# OnOnfre_Easy_Light_rev1.net
KiCad netlist of a schematic drawn in EAGLE
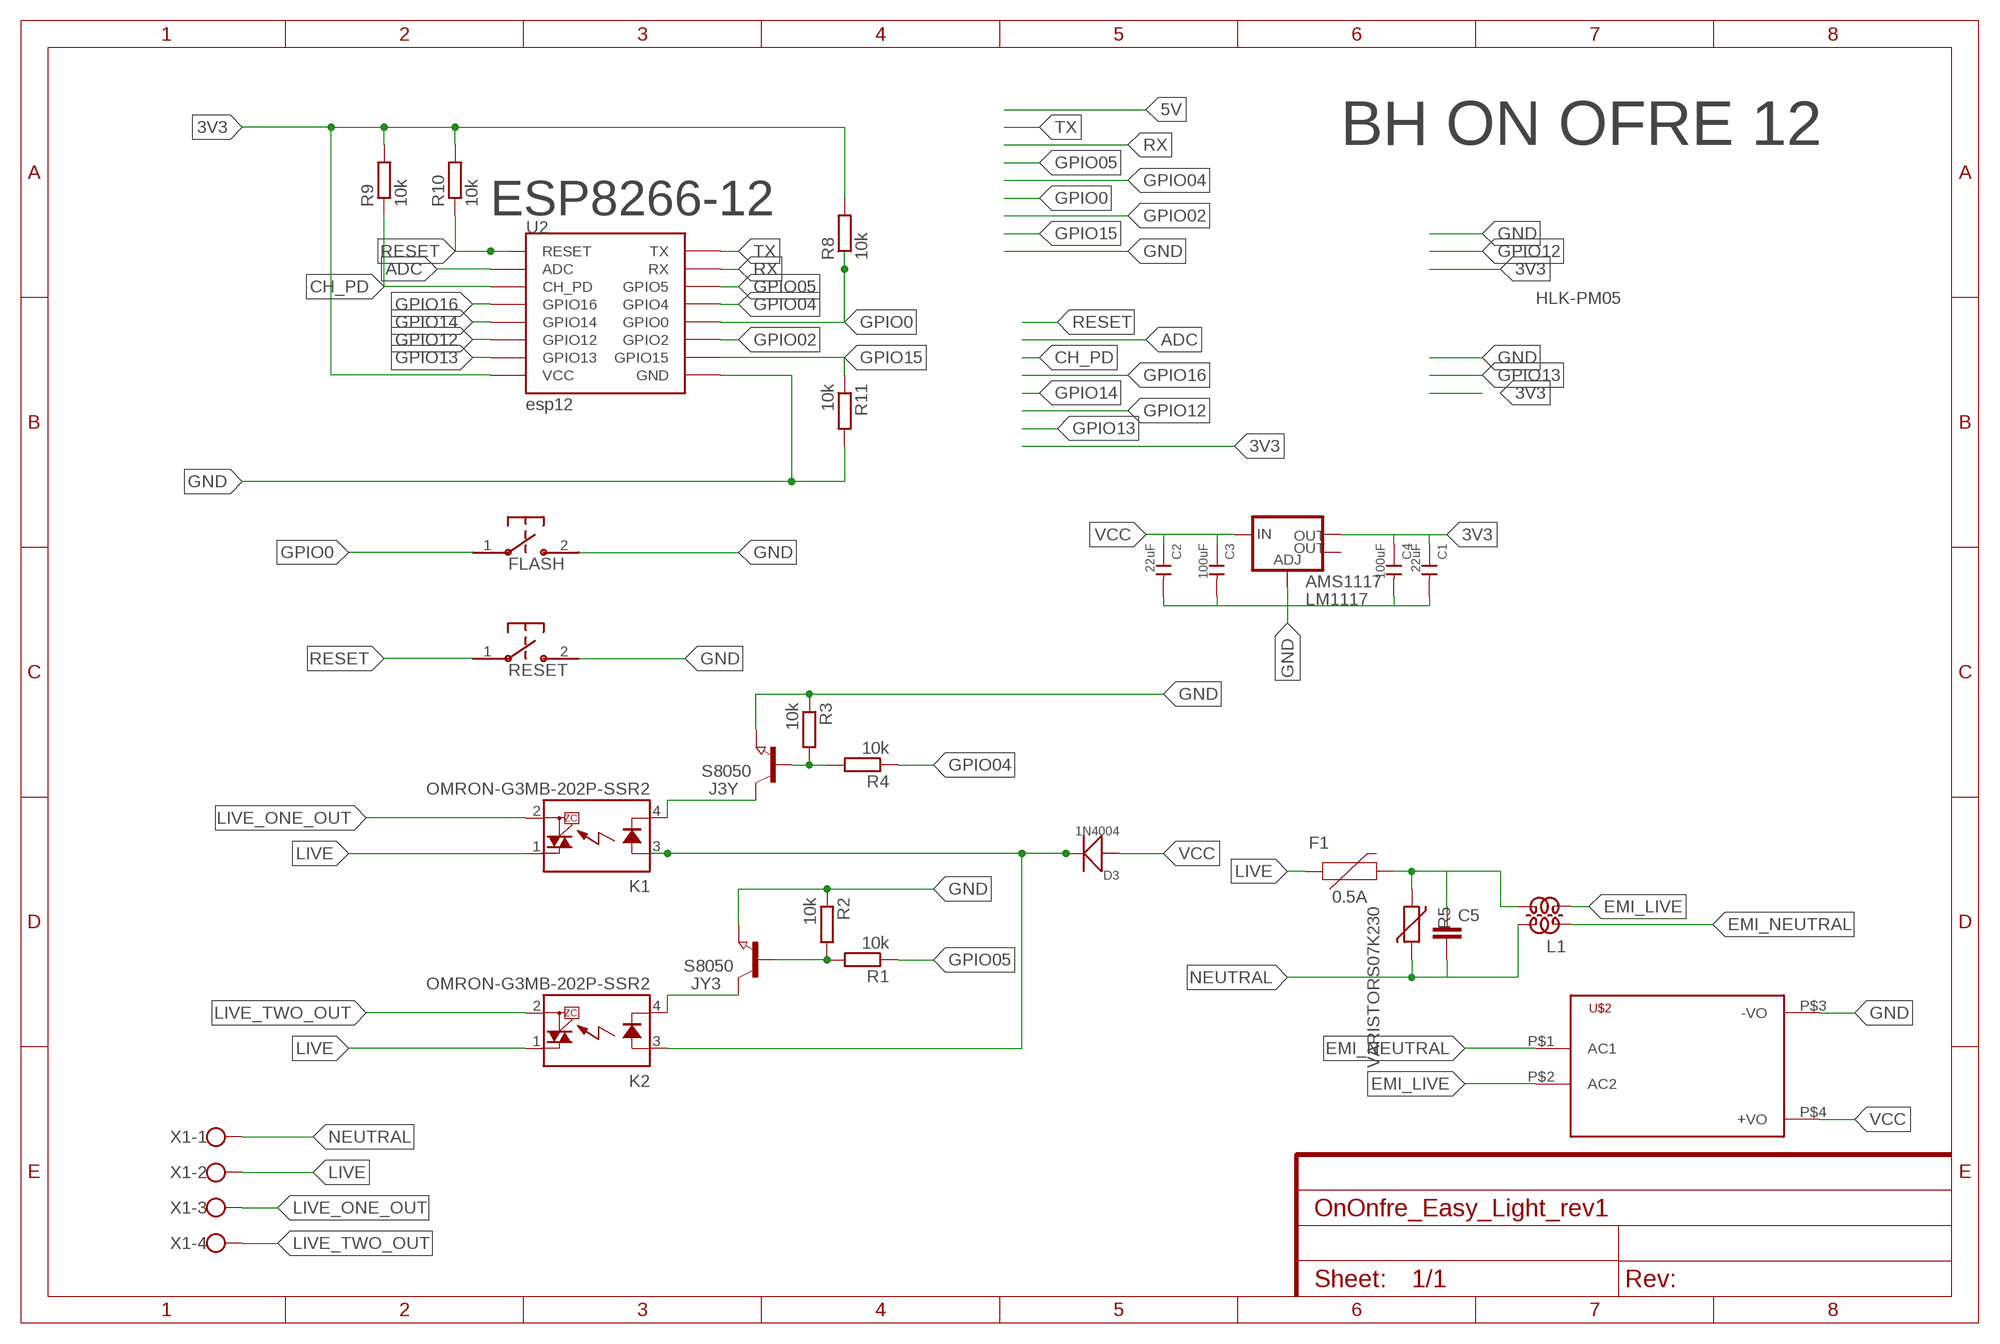
[diagram p0: schematic, sheet 1]

(export (version "E")
  (design (tool "Eeschema 10.0.6"))
  (components
    (comp (ref "AMS1117")
      (value "LM1117")
      (footprint "eagle-import:SOT223")
      (libsource (lib "eagle-import") (part "V_REG_LM1117SOT223"))
    )
    (comp (ref "C1")
      (value "22uF")
      (footprint "eagle-import:C1206")
      (fields (field (name "MPN") "CC1206KKX7RCBB102"))
      (libsource (lib "eagle-import") (part "CERAMIC-1NF-1KV-10%-X7R?(1206)"))
    )
    (comp (ref "C2")
      (value "22uF")
      (footprint "eagle-import:C1206")
      (fields (field (name "MPN") "CC1206KKX7RCBB102"))
      (libsource (lib "eagle-import") (part "CERAMIC-1NF-1KV-10%-X7R?(1206)"))
    )
    (comp (ref "C3")
      (value "100uF")
      (footprint "eagle-import:C1206")
      (fields (field (name "MPN") "CC1206KKX7RCBB102"))
      (libsource (lib "eagle-import") (part "CERAMIC-1NF-1KV-10%-X7R?(1206)"))
    )
    (comp (ref "C4")
      (value "100uF")
      (footprint "eagle-import:C1206")
      (fields (field (name "MPN") "CC1206KKX7RCBB102"))
      (libsource (lib "eagle-import") (part "CERAMIC-1NF-1KV-10%-X7R?(1206)"))
    )
    (comp (ref "C5")
      (value "C-EU102-054X133")
      (footprint "eagle-import:C102-054X133")
      (libsource (lib "eagle-import") (part "C-EU102-054X133"))
    )
    (comp (ref "D3")
      (value "1N4004")
      (footprint "eagle-import:DO-214AC")
      (fields (field (name "MPN") "1N4007"))
      (libsource (lib "eagle-import") (part "DIODE-GEN-PURPOSE-1KV-1A(DO-214AC)"))
    )
    (comp (ref "F1")
      (value "0.5A")
      (footprint "eagle-import:PTH")
      (libsource (lib "eagle-import") (part "PPTC_PTH"))
    )
    (comp (ref "FLASH")
      (value "B3U-1000P-2P-SMD")
      (footprint "eagle-import:B3U-1000P")
      (fields (field (name "MANUFACTURER") "Omron") (field (name "MPN") "B3U-1000P"))
      (libsource (lib "eagle-import") (part "B3U-1000P"))
    )
    (comp (ref "J3Y")
      (value "S8050")
      (footprint "eagle-import:SOT23")
      (libsource (lib "eagle-import") (part "NPN-TRANSISTOR_SOT23"))
    )
    (comp (ref "JY3")
      (value "S8050")
      (footprint "eagle-import:SOT23")
      (libsource (lib "eagle-import") (part "NPN-TRANSISTOR_SOT23"))
    )
    (comp (ref "K1")
      (value "OMRON-G3MB-202P-SSR2")
      (footprint "eagle-import:OMRON-G3MB-202P-SSR")
      (fields (field (name "MPN") "S202S02F"))
      (libsource (lib "eagle-import") (part "OMRON-G3MB-202P-SSR2"))
    )
    (comp (ref "K2")
      (value "OMRON-G3MB-202P-SSR2")
      (footprint "eagle-import:OMRON-G3MB-202P-SSR")
      (fields (field (name "MPN") "S202S02F"))
      (libsource (lib "eagle-import") (part "OMRON-G3MB-202P-SSR2"))
    )
    (comp (ref "L1")
      (value "ZD60820510")
      (footprint "eagle-import:ZD6-2X15")
      (libsource (lib "eagle-import") (part "ZD60820510"))
    )
    (comp (ref "R1")
      (value "10k")
      (footprint "eagle-import:R0603")
      (libsource (lib "eagle-import") (part "R-EU_R0603"))
    )
    (comp (ref "R2")
      (value "10k")
      (footprint "eagle-import:R0603")
      (libsource (lib "eagle-import") (part "R-EU_R0603"))
    )
    (comp (ref "R3")
      (value "10k")
      (footprint "eagle-import:R0603")
      (libsource (lib "eagle-import") (part "R-EU_R0603"))
    )
    (comp (ref "R4")
      (value "10k")
      (footprint "eagle-import:R0603")
      (libsource (lib "eagle-import") (part "R-EU_R0603"))
    )
    (comp (ref "R5")
      (value "VARISTORS07K230")
      (footprint "eagle-import:S07K230")
      (libsource (lib "eagle-import") (part "VARISTORS07K230"))
    )
    (comp (ref "R8")
      (value "10k")
      (footprint "eagle-import:R0603")
      (libsource (lib "eagle-import") (part "R-EU_R0603"))
    )
    (comp (ref "R9")
      (value "10k")
      (footprint "eagle-import:R0603")
      (libsource (lib "eagle-import") (part "R-EU_R0603"))
    )
    (comp (ref "R10")
      (value "10k")
      (footprint "eagle-import:R0603")
      (libsource (lib "eagle-import") (part "R-EU_R0603"))
    )
    (comp (ref "R11")
      (value "10k")
      (footprint "eagle-import:R0603")
      (libsource (lib "eagle-import") (part "R-EU_R0603"))
    )
    (comp (ref "RESET")
      (value "B3U-1000P-2P-SMD")
      (footprint "eagle-import:B3U-1000P")
      (fields (field (name "MANUFACTURER") "Omron") (field (name "MPN") "B3U-1000P"))
      (libsource (lib "eagle-import") (part "B3U-1000P"))
    )
    (comp (ref "U$2")
      (value "HKLPM01")
      (footprint "eagle-import:HKLPM01")
      (libsource (lib "eagle-import") (part "HKLPM01"))
    )
    (comp (ref "U2")
      (value "esp12")
      (footprint "eagle-import:ESP12-SMD")
      (libsource (lib "eagle-import") (part "ESP12SMD"))
    )
    (comp (ref "X1")
      (value "W237-4")
      (footprint "eagle-import:W237-4")
      (libsource (lib "eagle-import") (part "W237-4"))
    )
  )
  (nets
    (net (code "1") (name "3V3") (class "Default")
      (node (ref "AMS1117") (pin "2") (pinfunction "OUT_2") (pintype "output"))
      (node (ref "C1") (pin "1") (pinfunction "1_1") (pintype "passive"))
      (node (ref "C4") (pin "1") (pinfunction "1_1") (pintype "passive"))
      (node (ref "R10") (pin "2") (pinfunction "2_2") (pintype "passive"))
      (node (ref "R8") (pin "2") (pinfunction "2_2") (pintype "passive"))
      (node (ref "R9") (pin "2") (pinfunction "2_2") (pintype "passive"))
      (node (ref "U2") (pin "VCC") (pinfunction "VCC_VCC") (pintype "bidirectional"))
    )
    (net (code "2") (name "5V") (class "Default")
      (node (ref "D3") (pin "2") (pinfunction "-_2") (pintype "passive"))
      (node (ref "K1") (pin "3") (pinfunction "A_3") (pintype "passive"))
      (node (ref "K2") (pin "3") (pinfunction "A_3") (pintype "passive"))
    )
    (net (code "3") (name "ADC") (class "Default")
      (node (ref "U2") (pin "ADC") (pinfunction "ADC_ADC") (pintype "bidirectional"))
    )
    (net (code "4") (name "CH_PD") (class "Default")
      (node (ref "R9") (pin "1") (pinfunction "1_1") (pintype "passive"))
      (node (ref "U2") (pin "CH_PD") (pinfunction "CH_PD_CH_PD") (pintype "bidirectional"))
    )
    (net (code "5") (name "EMI_LIVE") (class "Default")
      (node (ref "L1") (pin "2") (pinfunction "2_2") (pintype "passive"))
      (node (ref "U$2") (pin "P$2") (pinfunction "AC2_P$2") (pintype "bidirectional"))
    )
    (net (code "6") (name "EMI_NEUTRAL") (class "Default")
      (node (ref "L1") (pin "1") (pinfunction "1_1") (pintype "passive"))
      (node (ref "U$2") (pin "P$1") (pinfunction "AC1_P$1") (pintype "bidirectional"))
    )
    (net (code "7") (name "GND") (class "Default")
      (node (ref "AMS1117") (pin "1") (pinfunction "ADJ_1") (pintype "input"))
      (node (ref "C1") (pin "2") (pinfunction "2_2") (pintype "passive"))
      (node (ref "C2") (pin "2") (pinfunction "2_2") (pintype "passive"))
      (node (ref "C3") (pin "2") (pinfunction "2_2") (pintype "passive"))
      (node (ref "C4") (pin "2") (pinfunction "2_2") (pintype "passive"))
      (node (ref "FLASH") (pin "2") (pinfunction "P$2_2") (pintype "passive"))
      (node (ref "J3Y") (pin "2") (pinfunction "E_2") (pintype "passive"))
      (node (ref "JY3") (pin "2") (pinfunction "E_2") (pintype "passive"))
      (node (ref "R11") (pin "2") (pinfunction "2_2") (pintype "passive"))
      (node (ref "R2") (pin "1") (pinfunction "1_1") (pintype "passive"))
      (node (ref "R3") (pin "1") (pinfunction "1_1") (pintype "passive"))
      (node (ref "RESET") (pin "2") (pinfunction "P$2_2") (pintype "passive"))
      (node (ref "U$2") (pin "P$3") (pinfunction "-VO_P$3") (pintype "bidirectional"))
      (node (ref "U2") (pin "GND") (pinfunction "GND_GND") (pintype "bidirectional"))
    )
    (net (code "8") (name "GPIO0") (class "Default")
      (node (ref "FLASH") (pin "1") (pinfunction "P$1_1") (pintype "passive"))
      (node (ref "R8") (pin "1") (pinfunction "1_1") (pintype "passive"))
      (node (ref "U2") (pin "GPIO0") (pinfunction "GPIO0_GPIO0") (pintype "bidirectional"))
    )
    (net (code "9") (name "GPIO02") (class "Default")
      (node (ref "U2") (pin "GPIO2") (pinfunction "GPIO2_GPIO2") (pintype "bidirectional"))
    )
    (net (code "10") (name "GPIO04") (class "Default")
      (node (ref "R4") (pin "1") (pinfunction "1_1") (pintype "passive"))
      (node (ref "U2") (pin "GPIO4") (pinfunction "GPIO4_GPIO4") (pintype "bidirectional"))
    )
    (net (code "11") (name "GPIO05") (class "Default")
      (node (ref "R1") (pin "1") (pinfunction "1_1") (pintype "passive"))
      (node (ref "U2") (pin "GPIO5") (pinfunction "GPIO5_GPIO5") (pintype "bidirectional"))
    )
    (net (code "12") (name "GPIO12") (class "Default")
      (node (ref "U2") (pin "GPIO12") (pinfunction "GPIO12_GPIO12") (pintype "bidirectional"))
    )
    (net (code "13") (name "GPIO13") (class "Default")
      (node (ref "U2") (pin "GPIO13") (pinfunction "GPIO13_GPIO13") (pintype "bidirectional"))
    )
    (net (code "14") (name "GPIO14") (class "Default")
      (node (ref "U2") (pin "GPIO14") (pinfunction "GPIO14_GPIO14") (pintype "bidirectional"))
    )
    (net (code "15") (name "GPIO15") (class "Default")
      (node (ref "R11") (pin "1") (pinfunction "1_1") (pintype "passive"))
      (node (ref "U2") (pin "GPIO15") (pinfunction "GPIO15_GPIO15") (pintype "bidirectional"))
    )
    (net (code "16") (name "GPIO16") (class "Default")
      (node (ref "U2") (pin "GPIO16") (pinfunction "GPIO16_GPIO16") (pintype "bidirectional"))
    )
    (net (code "17") (name "LIVE") (class "Default")
      (node (ref "F1") (pin "P$1") (pinfunction "1_P$1") (pintype "bidirectional"))
      (node (ref "K1") (pin "1") (pinfunction "DS1_1") (pintype "passive"))
      (node (ref "K2") (pin "1") (pinfunction "DS1_1") (pintype "passive"))
      (node (ref "X1") (pin "2") (pinfunction "KL_2") (pintype "passive"))
    )
    (net (code "18") (name "LIVE_ONE_OUT") (class "Default")
      (node (ref "K1") (pin "2") (pinfunction "DS2_2") (pintype "passive"))
      (node (ref "X1") (pin "3") (pinfunction "KL_3") (pintype "passive"))
    )
    (net (code "19") (name "LIVE_TWO_OUT") (class "Default")
      (node (ref "K2") (pin "2") (pinfunction "DS2_2") (pintype "passive"))
      (node (ref "X1") (pin "4") (pinfunction "KL_4") (pintype "passive"))
    )
    (net (code "20") (name "NEUTRAL") (class "Default")
      (node (ref "C5") (pin "2") (pinfunction "2_2") (pintype "passive"))
      (node (ref "L1") (pin "4") (pinfunction "4_4") (pintype "passive"))
      (node (ref "R5") (pin "1") (pinfunction "1_1") (pintype "passive"))
      (node (ref "X1") (pin "1") (pinfunction "KL_1") (pintype "passive"))
    )
    (net (code "21") (name "Net-(F1-2)") (class "Default")
      (node (ref "C5") (pin "1") (pinfunction "1_1") (pintype "passive"))
      (node (ref "F1") (pin "P$2") (pinfunction "2_P$2") (pintype "bidirectional"))
      (node (ref "L1") (pin "3") (pinfunction "3_3") (pintype "passive"))
      (node (ref "R5") (pin "2") (pinfunction "2_2") (pintype "passive"))
    )
    (net (code "22") (name "Net-(J3Y-B)") (class "Default")
      (node (ref "J3Y") (pin "1") (pinfunction "B_1") (pintype "passive"))
      (node (ref "R3") (pin "2") (pinfunction "2_2") (pintype "passive"))
      (node (ref "R4") (pin "2") (pinfunction "2_2") (pintype "passive"))
    )
    (net (code "23") (name "Net-(J3Y-C)") (class "Default")
      (node (ref "J3Y") (pin "3") (pinfunction "C_3") (pintype "passive"))
      (node (ref "K1") (pin "4") (pinfunction "K_4") (pintype "passive"))
    )
    (net (code "24") (name "Net-(JY3-B)") (class "Default")
      (node (ref "JY3") (pin "1") (pinfunction "B_1") (pintype "passive"))
      (node (ref "R1") (pin "2") (pinfunction "2_2") (pintype "passive"))
      (node (ref "R2") (pin "2") (pinfunction "2_2") (pintype "passive"))
    )
    (net (code "25") (name "Net-(JY3-C)") (class "Default")
      (node (ref "JY3") (pin "3") (pinfunction "C_3") (pintype "passive"))
      (node (ref "K2") (pin "4") (pinfunction "K_4") (pintype "passive"))
    )
    (net (code "26") (name "RESET") (class "Default")
      (node (ref "R10") (pin "1") (pinfunction "1_1") (pintype "passive"))
      (node (ref "RESET") (pin "1") (pinfunction "P$1_1") (pintype "passive"))
      (node (ref "U2") (pin "RESET") (pinfunction "RESET_RESET") (pintype "bidirectional"))
    )
    (net (code "27") (name "RX") (class "Default")
      (node (ref "U2") (pin "RXD0") (pinfunction "RX_RXD0") (pintype "bidirectional"))
    )
    (net (code "28") (name "TX") (class "Default")
      (node (ref "U2") (pin "TXD0") (pinfunction "TX_TXD0") (pintype "bidirectional"))
    )
    (net (code "29") (name "VCC") (class "Default")
      (node (ref "AMS1117") (pin "3") (pinfunction "IN_3") (pintype "input"))
      (node (ref "C2") (pin "1") (pinfunction "1_1") (pintype "passive"))
      (node (ref "C3") (pin "1") (pinfunction "1_1") (pintype "passive"))
      (node (ref "D3") (pin "1") (pinfunction "+_1") (pintype "passive"))
      (node (ref "U$2") (pin "P$4") (pinfunction "+VO_P$4") (pintype "bidirectional"))
    )
    (net (code "30") (name "unconnected-(AMS1117-OUT-Pad4)") (class "Default")
      (node (ref "AMS1117") (pin "4") (pinfunction "OUT_4") (pintype "output"))
    )
  )
)
